# picstick_25k50_v1.net
KiCad netlist of a schematic drawn in EAGLE
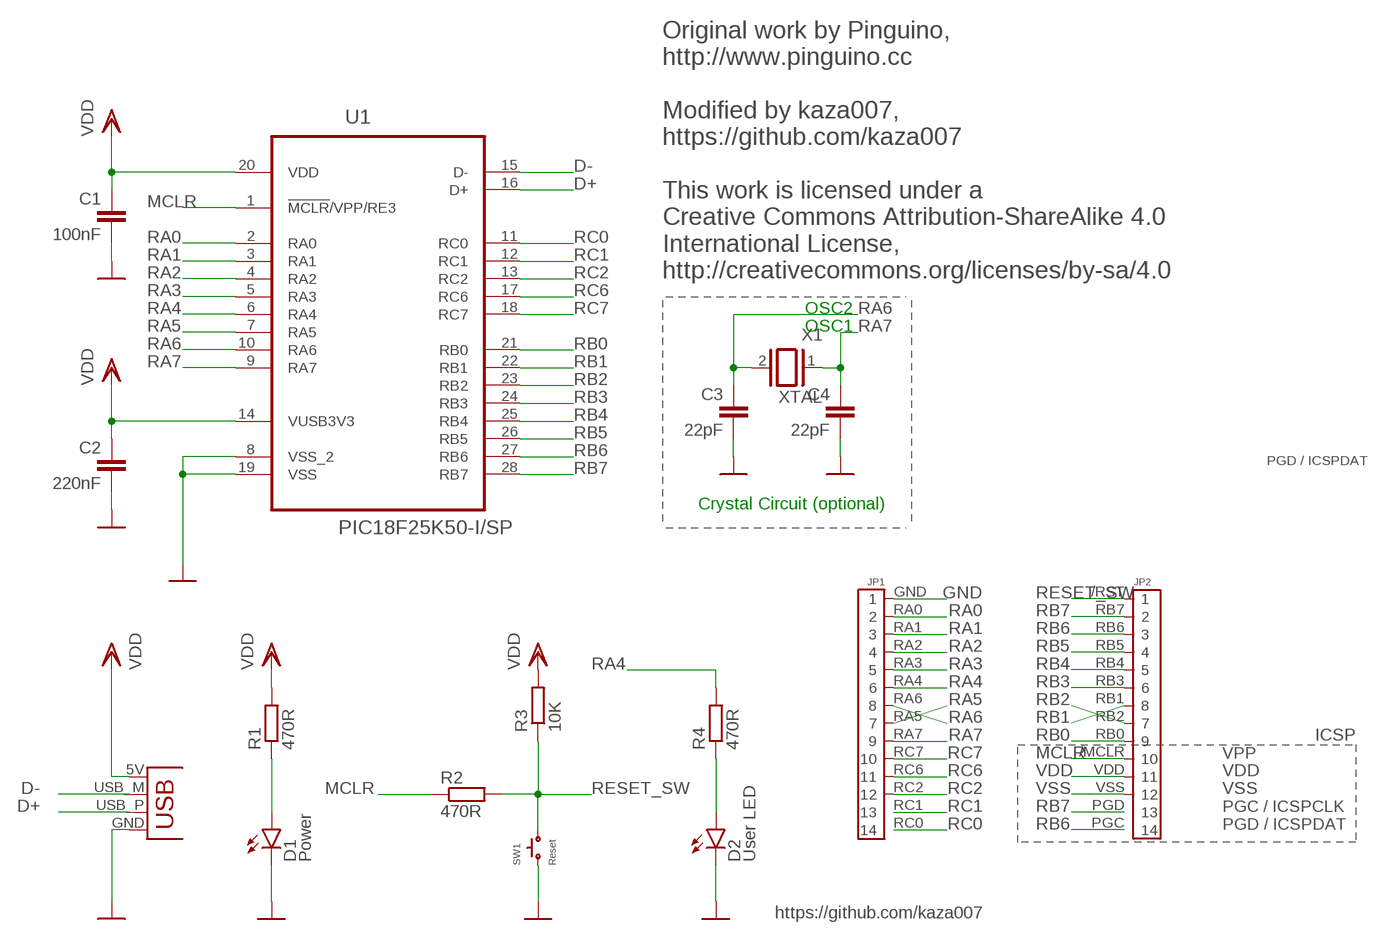
[diagram p0: schematic, sheet 1]

(export (version "E")
  (design (tool "Eeschema 10.0.6"))
  (components
    (comp (ref "C1")
      (value "100nF")
      (footprint "eagle-import:C050-024X044")
      (libsource (lib "eagle-import") (part "C-EU050-024X044"))
    )
    (comp (ref "C2")
      (value "220nF")
      (footprint "eagle-import:C050-024X044")
      (libsource (lib "eagle-import") (part "C-EU050-024X044"))
    )
    (comp (ref "C3")
      (value "22pF")
      (footprint "eagle-import:C025-024X044")
      (libsource (lib "eagle-import") (part "C-EU025-024X044"))
    )
    (comp (ref "C4")
      (value "22pF")
      (footprint "eagle-import:C025-024X044")
      (libsource (lib "eagle-import") (part "C-EU025-024X044"))
    )
    (comp (ref "D1")
      (value "Power")
      (footprint "eagle-import:LED3MM")
      (libsource (lib "eagle-import") (part "LED3MM"))
    )
    (comp (ref "D2")
      (value "User LED")
      (footprint "eagle-import:LED3MM")
      (libsource (lib "eagle-import") (part "LED3MM"))
    )
    (comp (ref "JP1")
      (value "CONN-14P-PICSTICK-JP1")
      (footprint "eagle-import:PICSTICK_JP1")
      (libsource (lib "eagle-import") (part "CONN-14P-PICSTICK-JP1"))
    )
    (comp (ref "JP2")
      (value "CONN-14P-PICSTICK-JP2")
      (footprint "eagle-import:PICSTICK_JP2")
      (libsource (lib "eagle-import") (part "CONN-14P-PICSTICK-JP2"))
    )
    (comp (ref "R1")
      (value "470R")
      (footprint "eagle-import:0204_7")
      (libsource (lib "eagle-import") (part "R-EU_0204/7"))
    )
    (comp (ref "R2")
      (value "470R")
      (footprint "eagle-import:0204_7")
      (libsource (lib "eagle-import") (part "R-EU_0204/7"))
    )
    (comp (ref "R3")
      (value "10K")
      (footprint "eagle-import:0204_7")
      (libsource (lib "eagle-import") (part "R-EU_0204/7"))
    )
    (comp (ref "R4")
      (value "470R")
      (footprint "eagle-import:0204_7")
      (libsource (lib "eagle-import") (part "R-EU_0204/7"))
    )
    (comp (ref "SW1")
      (value "Reset")
      (footprint "eagle-import:SKHLAAA010")
      (libsource (lib "eagle-import") (part "SKHLAAA010"))
    )
    (comp (ref "U1")
      (value "PIC18F25K50-I/SP")
      (footprint "eagle-import:DIP254P762X406-28P")
      (libsource (lib "eagle-import") (part "PIC18F25K50-I/SP"))
    )
    (comp (ref "USB")
      (value "FREETRONICS-MASTER-V1_USBPCB")
      (footprint "eagle-import:FREETRONICS-MASTER-V1_USB-A-PCB")
      (libsource (lib "eagle-import") (part "FREETRONICS-MASTER-V1_USBPCB"))
    )
    (comp (ref "X1")
      (value "XTAL")
      (footprint "eagle-import:QS")
      (libsource (lib "eagle-import") (part "XTAL/S"))
    )
  )
  (nets
    (net (code "1") (name "/D+") (class "Default")
      (node (ref "U1") (pin "16") (pinfunction "D+_16") (pintype "passive"))
      (node (ref "USB") (pin "USB_P") (pinfunction "D+_USB_P") (pintype "bidirectional"))
    )
    (net (code "2") (name "/D-") (class "Default")
      (node (ref "U1") (pin "15") (pinfunction "D-_15") (pintype "passive"))
      (node (ref "USB") (pin "USB_M") (pinfunction "D-_USB_M") (pintype "bidirectional"))
    )
    (net (code "3") (name "/MCLR") (class "Default")
      (node (ref "JP2") (pin "/MCLR") (pinfunction "10_/MCLR") (pintype "bidirectional"))
      (node (ref "R2") (pin "1") (pinfunction "1_1") (pintype "passive"))
      (node (ref "U1") (pin "1") (pinfunction "~{MCLR}/VPP/RE3_1") (pintype "input"))
    )
    (net (code "4") (name "/RA0") (class "Default")
      (node (ref "JP1") (pin "RA0") (pinfunction "2_RA0") (pintype "bidirectional"))
      (node (ref "U1") (pin "2") (pinfunction "RA0_2") (pintype "bidirectional"))
    )
    (net (code "5") (name "/RA1") (class "Default")
      (node (ref "JP1") (pin "RA1") (pinfunction "3_RA1") (pintype "bidirectional"))
      (node (ref "U1") (pin "3") (pinfunction "RA1_3") (pintype "bidirectional"))
    )
    (net (code "6") (name "/RA2") (class "Default")
      (node (ref "JP1") (pin "RA2") (pinfunction "4_RA2") (pintype "bidirectional"))
      (node (ref "U1") (pin "4") (pinfunction "RA2_4") (pintype "bidirectional"))
    )
    (net (code "7") (name "/RA3") (class "Default")
      (node (ref "JP1") (pin "RA3") (pinfunction "5_RA3") (pintype "bidirectional"))
      (node (ref "U1") (pin "5") (pinfunction "RA3_5") (pintype "bidirectional"))
    )
    (net (code "8") (name "/RA4") (class "Default")
      (node (ref "JP1") (pin "RA4") (pinfunction "6_RA4") (pintype "bidirectional"))
      (node (ref "R4") (pin "2") (pinfunction "2_2") (pintype "passive"))
      (node (ref "U1") (pin "6") (pinfunction "RA4_6") (pintype "bidirectional"))
    )
    (net (code "9") (name "/RA5") (class "Default")
      (node (ref "JP1") (pin "RA5") (pinfunction "7_RA5") (pintype "bidirectional"))
      (node (ref "U1") (pin "7") (pinfunction "RA5_7") (pintype "bidirectional"))
    )
    (net (code "10") (name "/RA6") (class "Default")
      (node (ref "C3") (pin "1") (pinfunction "1_1") (pintype "passive"))
      (node (ref "JP1") (pin "RA6") (pinfunction "8_RA6") (pintype "bidirectional"))
      (node (ref "U1") (pin "10") (pinfunction "RA6_10") (pintype "bidirectional"))
      (node (ref "X1") (pin "2") (pinfunction "2_2") (pintype "passive"))
    )
    (net (code "11") (name "/RA7") (class "Default")
      (node (ref "C4") (pin "1") (pinfunction "1_1") (pintype "passive"))
      (node (ref "JP1") (pin "RA7") (pinfunction "9_RA7") (pintype "bidirectional"))
      (node (ref "U1") (pin "9") (pinfunction "RA7_9") (pintype "bidirectional"))
      (node (ref "X1") (pin "1") (pinfunction "1_1") (pintype "passive"))
    )
    (net (code "12") (name "/RB0") (class "Default")
      (node (ref "JP2") (pin "RB0") (pinfunction "9_RB0") (pintype "bidirectional"))
      (node (ref "U1") (pin "21") (pinfunction "RB0_21") (pintype "bidirectional"))
    )
    (net (code "13") (name "/RB1") (class "Default")
      (node (ref "JP2") (pin "RB1") (pinfunction "8_RB1") (pintype "bidirectional"))
      (node (ref "U1") (pin "22") (pinfunction "RB1_22") (pintype "bidirectional"))
    )
    (net (code "14") (name "/RB2") (class "Default")
      (node (ref "JP2") (pin "RB2") (pinfunction "7_RB2") (pintype "bidirectional"))
      (node (ref "U1") (pin "23") (pinfunction "RB2_23") (pintype "bidirectional"))
    )
    (net (code "15") (name "/RB3") (class "Default")
      (node (ref "JP2") (pin "RB3") (pinfunction "6_RB3") (pintype "bidirectional"))
      (node (ref "U1") (pin "24") (pinfunction "RB3_24") (pintype "bidirectional"))
    )
    (net (code "16") (name "/RB4") (class "Default")
      (node (ref "JP2") (pin "RB4") (pinfunction "5_RB4") (pintype "bidirectional"))
      (node (ref "U1") (pin "25") (pinfunction "RB4_25") (pintype "bidirectional"))
    )
    (net (code "17") (name "/RB5") (class "Default")
      (node (ref "JP2") (pin "RB5") (pinfunction "4_RB5") (pintype "bidirectional"))
      (node (ref "U1") (pin "26") (pinfunction "RB5_26") (pintype "bidirectional"))
    )
    (net (code "18") (name "/RB6") (class "Default")
      (node (ref "JP2") (pin "PGC") (pinfunction "14_PGC") (pintype "bidirectional"))
      (node (ref "JP2") (pin "RB6") (pinfunction "3_RB6") (pintype "bidirectional"))
      (node (ref "U1") (pin "27") (pinfunction "RB6_27") (pintype "bidirectional"))
    )
    (net (code "19") (name "/RB7") (class "Default")
      (node (ref "JP2") (pin "PGD") (pinfunction "13_PGD") (pintype "bidirectional"))
      (node (ref "JP2") (pin "RB7") (pinfunction "2_RB7") (pintype "bidirectional"))
      (node (ref "U1") (pin "28") (pinfunction "RB7_28") (pintype "bidirectional"))
    )
    (net (code "20") (name "/RC0") (class "Default")
      (node (ref "JP1") (pin "RC0") (pinfunction "14_RC0") (pintype "bidirectional"))
      (node (ref "U1") (pin "11") (pinfunction "RC0_11") (pintype "bidirectional"))
    )
    (net (code "21") (name "/RC1") (class "Default")
      (node (ref "JP1") (pin "RC1") (pinfunction "13_RC1") (pintype "bidirectional"))
      (node (ref "U1") (pin "12") (pinfunction "RC1_12") (pintype "bidirectional"))
    )
    (net (code "22") (name "/RC2") (class "Default")
      (node (ref "JP1") (pin "RC2") (pinfunction "12_RC2") (pintype "bidirectional"))
      (node (ref "U1") (pin "13") (pinfunction "RC2_13") (pintype "bidirectional"))
    )
    (net (code "23") (name "/RC6") (class "Default")
      (node (ref "JP1") (pin "RC6") (pinfunction "11_RC6") (pintype "bidirectional"))
      (node (ref "U1") (pin "17") (pinfunction "RC6_17") (pintype "bidirectional"))
    )
    (net (code "24") (name "/RC7") (class "Default")
      (node (ref "JP1") (pin "RC7") (pinfunction "10_RC7") (pintype "bidirectional"))
      (node (ref "U1") (pin "18") (pinfunction "RC7_18") (pintype "bidirectional"))
    )
    (net (code "25") (name "/RESET_SW") (class "Default")
      (node (ref "JP2") (pin "/RST") (pinfunction "1_/RST") (pintype "bidirectional"))
      (node (ref "R2") (pin "2") (pinfunction "2_2") (pintype "passive"))
      (node (ref "R3") (pin "1") (pinfunction "1_1") (pintype "passive"))
      (node (ref "SW1") (pin "2") (pinfunction "2_2") (pintype "bidirectional"))
    )
    (net (code "26") (name "/VSS") (class "Default")
      (node (ref "JP2") (pin "VSS") (pinfunction "12_VSS") (pintype "bidirectional"))
    )
    (net (code "27") (name "Net-(D1-PadA)") (class "Default")
      (node (ref "D1") (pin "A") (pinfunction "A_A") (pintype "passive"))
      (node (ref "R1") (pin "1") (pinfunction "1_1") (pintype "passive"))
    )
    (net (code "28") (name "Net-(D2-PadA)") (class "Default")
      (node (ref "D2") (pin "A") (pinfunction "A_A") (pintype "passive"))
      (node (ref "R4") (pin "1") (pinfunction "1_1") (pintype "passive"))
    )
    (net (code "29") (name "SUPPLY1_GND") (class "Default")
      (node (ref "C1") (pin "2") (pinfunction "2_2") (pintype "passive"))
      (node (ref "C2") (pin "2") (pinfunction "2_2") (pintype "passive"))
      (node (ref "C3") (pin "2") (pinfunction "2_2") (pintype "passive"))
      (node (ref "C4") (pin "2") (pinfunction "2_2") (pintype "passive"))
      (node (ref "D1") (pin "K") (pinfunction "C_K") (pintype "passive"))
      (node (ref "D2") (pin "K") (pinfunction "C_K") (pintype "passive"))
      (node (ref "JP1") (pin "GND") (pinfunction "1_GND") (pintype "bidirectional"))
      (node (ref "SW1") (pin "1") (pinfunction "1_1") (pintype "bidirectional"))
      (node (ref "U1") (pin "19") (pinfunction "VSS_19") (pintype "power_in"))
      (node (ref "U1") (pin "8") (pinfunction "VSS_2_8") (pintype "power_in"))
      (node (ref "USB") (pin "GND") (pinfunction "GND_GND") (pintype "bidirectional"))
    )
    (net (code "30") (name "VDD") (class "Default")
      (node (ref "C1") (pin "1") (pinfunction "1_1") (pintype "passive"))
      (node (ref "C2") (pin "1") (pinfunction "1_1") (pintype "passive"))
      (node (ref "JP2") (pin "VDD") (pinfunction "11_VDD") (pintype "bidirectional"))
      (node (ref "R1") (pin "2") (pinfunction "2_2") (pintype "passive"))
      (node (ref "R3") (pin "2") (pinfunction "2_2") (pintype "passive"))
      (node (ref "U1") (pin "14") (pinfunction "VUSB3V3_14") (pintype "passive"))
      (node (ref "U1") (pin "20") (pinfunction "VDD_20") (pintype "power_in"))
      (node (ref "USB") (pin "5V") (pinfunction "VBUS_5V") (pintype "bidirectional"))
    )
  )
)
